# Si4844-A10_Radio_LM386_6-25_8_11.net
KiCad netlist of a schematic drawn in EAGLE
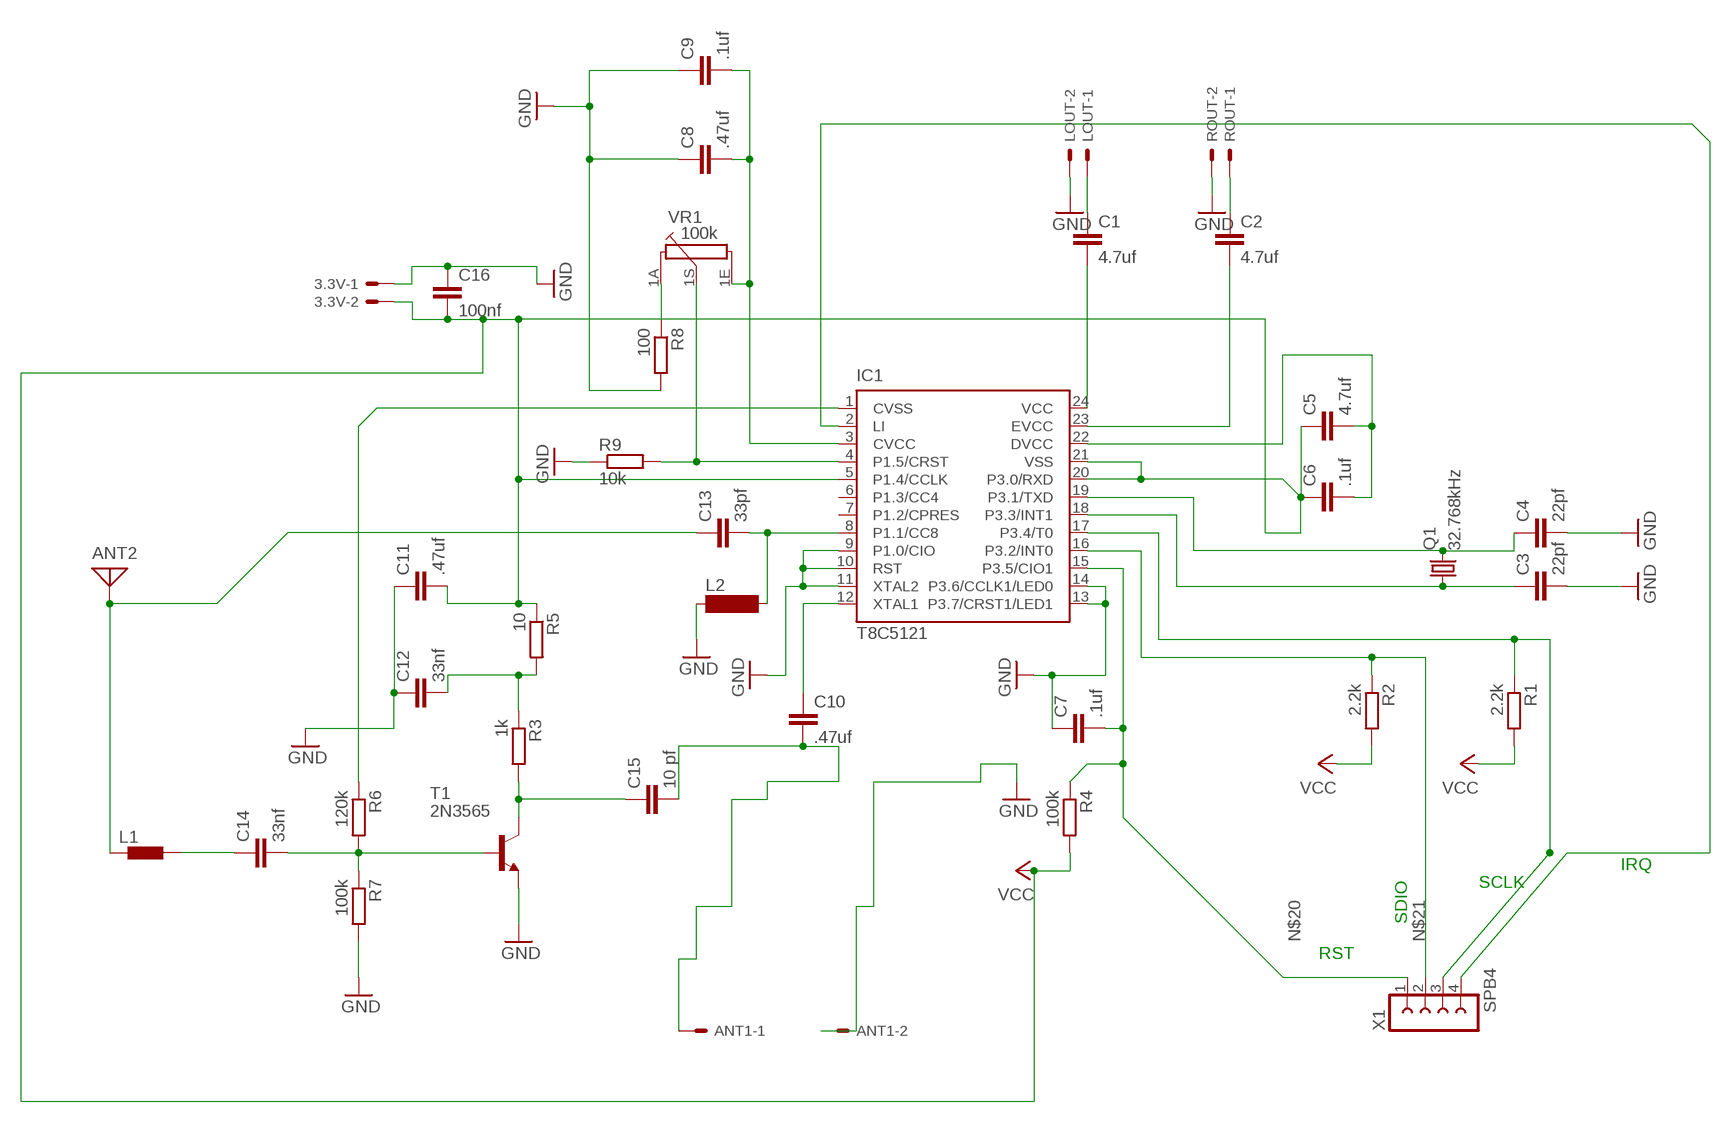
[diagram p0: schematic, sheet 1]

(export (version "E")
  (design (tool "Eeschema 10.0.6"))
  (components
    (comp (ref "3.3V")
      (value "22-23-2021")
      (footprint "eagle-import:22-23-2021")
      (fields (field (name "MF") "MOLEX"))
      (libsource (lib "eagle-import") (part "22-23-2021"))
    )
    (comp (ref "ANT1")
      (value "332-02")
      (footprint "eagle-import:332-02")
      (libsource (lib "eagle-import") (part "332-02"))
    )
    (comp (ref "ANT2")
      (value "ANTENNA")
      (footprint "eagle-import:PAD-01")
      (libsource (lib "eagle-import") (part "ANTENNA"))
    )
    (comp (ref "C1")
      (value "4.7uf")
      (footprint "eagle-import:C2.5-2")
      (libsource (lib "eagle-import") (part "C2.5/2"))
    )
    (comp (ref "C2")
      (value "4.7uf")
      (footprint "eagle-import:C2.5-2")
      (libsource (lib "eagle-import") (part "C2.5/2"))
    )
    (comp (ref "C3")
      (value "22pf")
      (footprint "eagle-import:C2.5-2")
      (libsource (lib "eagle-import") (part "C2.5/2"))
    )
    (comp (ref "C4")
      (value "22pf")
      (footprint "eagle-import:C2.5-2")
      (libsource (lib "eagle-import") (part "C2.5/2"))
    )
    (comp (ref "C5")
      (value "4.7uf")
      (footprint "eagle-import:C2.5-2")
      (libsource (lib "eagle-import") (part "C2.5/2"))
    )
    (comp (ref "C6")
      (value ".1uf")
      (footprint "eagle-import:C2.5-2")
      (libsource (lib "eagle-import") (part "C2.5/2"))
    )
    (comp (ref "C7")
      (value ".1uf")
      (footprint "eagle-import:C2.5-2")
      (libsource (lib "eagle-import") (part "C2.5/2"))
    )
    (comp (ref "C8")
      (value ".47uf")
      (footprint "eagle-import:C2.5-2")
      (libsource (lib "eagle-import") (part "C2.5/2"))
    )
    (comp (ref "C9")
      (value ".1uf")
      (footprint "eagle-import:C2.5-2")
      (libsource (lib "eagle-import") (part "C2.5/2"))
    )
    (comp (ref "C10")
      (value ".47uf")
      (footprint "eagle-import:C2.5-2")
      (libsource (lib "eagle-import") (part "C2.5/2"))
    )
    (comp (ref "C11")
      (value ".47uf")
      (footprint "eagle-import:C2.5-3")
      (libsource (lib "eagle-import") (part "C2,5-3"))
    )
    (comp (ref "C12")
      (value "33nf")
      (footprint "eagle-import:C2.5-3")
      (libsource (lib "eagle-import") (part "C2,5-3"))
    )
    (comp (ref "C13")
      (value "33pf")
      (footprint "eagle-import:C2.5-3")
      (libsource (lib "eagle-import") (part "C2,5-3"))
    )
    (comp (ref "C14")
      (value "33nf")
      (footprint "eagle-import:C2.5-3")
      (libsource (lib "eagle-import") (part "C2,5-3"))
    )
    (comp (ref "C15")
      (value "10 pf")
      (footprint "eagle-import:C2.5-3")
      (libsource (lib "eagle-import") (part "C2,5-3"))
    )
    (comp (ref "C16")
      (value "100nf")
      (footprint "eagle-import:C2.5-2")
      (libsource (lib "eagle-import") (part "C2.5/2"))
    )
    (comp (ref "IC1")
      (value "T8C5121")
      (footprint "eagle-import:SSOP24")
      (libsource (lib "eagle-import") (part "T8C5121"))
    )
    (comp (ref "L1")
      (value "BLM15HB121SN1")
      (footprint "eagle-import:0402")
      (libsource (lib "eagle-import") (part "BLM15HB121SN1"))
    )
    (comp (ref "L2")
      (value "SM-1206")
      (footprint "eagle-import:SM-1206")
      (libsource (lib "eagle-import") (part "SM-1206"))
    )
    (comp (ref "LOUT")
      (value "22-23-2021")
      (footprint "eagle-import:22-23-2021")
      (fields (field (name "MF") "MOLEX"))
      (libsource (lib "eagle-import") (part "22-23-2021"))
    )
    (comp (ref "Q1")
      (value "32.768kHz")
      (footprint "eagle-import:TC26V")
      (libsource (lib "eagle-import") (part "CRYSTALTC26V"))
    )
    (comp (ref "R1")
      (value "2.2k")
      (footprint "eagle-import:0204_7")
      (libsource (lib "eagle-import") (part "R-EU_0204/7"))
    )
    (comp (ref "R2")
      (value "2.2k")
      (footprint "eagle-import:0204_7")
      (libsource (lib "eagle-import") (part "R-EU_0204/7"))
    )
    (comp (ref "R3")
      (value "1k")
      (footprint "eagle-import:0204_7")
      (libsource (lib "eagle-import") (part "R-EU_0204/7"))
    )
    (comp (ref "R4")
      (value "100k")
      (footprint "eagle-import:0204_7")
      (libsource (lib "eagle-import") (part "R-EU_0204/7"))
    )
    (comp (ref "R5")
      (value "10")
      (footprint "eagle-import:0204_7")
      (libsource (lib "eagle-import") (part "R-EU_0204/7"))
    )
    (comp (ref "R6")
      (value "120k")
      (footprint "eagle-import:0204_7")
      (libsource (lib "eagle-import") (part "R-EU_0204/7"))
    )
    (comp (ref "R7")
      (value "100k")
      (footprint "eagle-import:0204_7")
      (libsource (lib "eagle-import") (part "R-EU_0204/7"))
    )
    (comp (ref "R8")
      (value "100")
      (footprint "eagle-import:0204_7")
      (libsource (lib "eagle-import") (part "R-EU_0204/7"))
    )
    (comp (ref "R9")
      (value "10k")
      (footprint "eagle-import:0204_7")
      (libsource (lib "eagle-import") (part "R-EU_0204/7"))
    )
    (comp (ref "ROUT")
      (value "22-23-2021")
      (footprint "eagle-import:22-23-2021")
      (fields (field (name "MF") "MOLEX"))
      (libsource (lib "eagle-import") (part "22-23-2021"))
    )
    (comp (ref "T1")
      (value "2N3565")
      (footprint "eagle-import:TO92")
      (libsource (lib "eagle-import") (part "2N3565"))
    )
    (comp (ref "VR1")
      (value "100k")
      (footprint "eagle-import:PC16S")
      (libsource (lib "eagle-import") (part "PC16S"))
    )
    (comp (ref "X1")
      (value "SPB4")
      (footprint "eagle-import:SPB4")
      (libsource (lib "eagle-import") (part "SPB4"))
    )
  )
  (nets
    (net (code "1") (name "/N$20") (class "Default")
      (node (ref "C7") (pin "2") (pinfunction "2_2") (pintype "passive"))
      (node (ref "IC1") (pin "15") (pinfunction "P3.5/CIO1_15") (pintype "bidirectional"))
      (node (ref "R4") (pin "1") (pinfunction "1_1") (pintype "passive"))
      (node (ref "X1") (pin "1") (pinfunction "1_1") (pintype "passive"))
    )
    (net (code "2") (name "/N$21") (class "Default")
      (node (ref "IC1") (pin "16") (pinfunction "P3.2/INT0_16") (pintype "bidirectional"))
      (node (ref "R2") (pin "1") (pinfunction "1_1") (pintype "passive"))
      (node (ref "X1") (pin "2") (pinfunction "2_2") (pintype "passive"))
    )
    (net (code "3") (name "GND") (class "Default")
      (node (ref "3.3V") (pin "1") (pinfunction "S_1") (pintype "passive"))
      (node (ref "ANT1") (pin "2") (pinfunction "S_2") (pintype "passive"))
      (node (ref "C11") (pin "1") (pinfunction "1_1") (pintype "passive"))
      (node (ref "C12") (pin "1") (pinfunction "1_1") (pintype "passive"))
      (node (ref "C16") (pin "1") (pinfunction "1_1") (pintype "passive"))
      (node (ref "C3") (pin "2") (pinfunction "2_2") (pintype "passive"))
      (node (ref "C4") (pin "2") (pinfunction "2_2") (pintype "passive"))
      (node (ref "C7") (pin "1") (pinfunction "1_1") (pintype "passive"))
      (node (ref "C8") (pin "1") (pinfunction "1_1") (pintype "passive"))
      (node (ref "C9") (pin "1") (pinfunction "1_1") (pintype "passive"))
      (node (ref "IC1") (pin "10") (pinfunction "RST_10") (pintype "bidirectional"))
      (node (ref "IC1") (pin "11") (pinfunction "XTAL2_11") (pintype "input"))
      (node (ref "IC1") (pin "13") (pinfunction "P3.7/CRST1/LED1_13") (pintype "bidirectional"))
      (node (ref "IC1") (pin "14") (pinfunction "P3.6/CCLK1/LED0_14") (pintype "bidirectional"))
      (node (ref "IC1") (pin "9") (pinfunction "P1.0/CIO_9") (pintype "bidirectional"))
      (node (ref "L2") (pin "1") (pinfunction "1_1") (pintype "passive"))
      (node (ref "LOUT") (pin "2") (pinfunction "S_2") (pintype "passive"))
      (node (ref "R7") (pin "2") (pinfunction "2_2") (pintype "passive"))
      (node (ref "R8") (pin "2") (pinfunction "2_2") (pintype "passive"))
      (node (ref "R9") (pin "1") (pinfunction "1_1") (pintype "passive"))
      (node (ref "ROUT") (pin "2") (pinfunction "S_2") (pintype "passive"))
      (node (ref "T1") (pin "3") (pinfunction "E_3") (pintype "passive"))
    )
    (net (code "4") (name "Net-(ANT1A-S)") (class "Default")
      (node (ref "ANT1") (pin "1") (pinfunction "S_1") (pintype "passive"))
      (node (ref "C10") (pin "2") (pinfunction "2_2") (pintype "passive"))
      (node (ref "C15") (pin "2") (pinfunction "2_2") (pintype "passive"))
    )
    (net (code "5") (name "Net-(ANT2-Pad1)") (class "Default")
      (node (ref "ANT2") (pin "1") (pinfunction "1_1") (pintype "output"))
      (node (ref "C13") (pin "1") (pinfunction "1_1") (pintype "passive"))
      (node (ref "L1") (pin "1") (pinfunction "1_1") (pintype "passive"))
    )
    (net (code "6") (name "Net-(C12-Pad2)") (class "Default")
      (node (ref "C12") (pin "2") (pinfunction "2_2") (pintype "passive"))
      (node (ref "R3") (pin "1") (pinfunction "1_1") (pintype "passive"))
      (node (ref "R5") (pin "2") (pinfunction "2_2") (pintype "passive"))
    )
    (net (code "7") (name "Net-(C14-Pad1)") (class "Default")
      (node (ref "C14") (pin "1") (pinfunction "1_1") (pintype "passive"))
      (node (ref "L1") (pin "2") (pinfunction "2_2") (pintype "passive"))
    )
    (net (code "8") (name "Net-(IC1-CVCC)") (class "Default")
      (node (ref "C8") (pin "2") (pinfunction "2_2") (pintype "passive"))
      (node (ref "C9") (pin "2") (pinfunction "2_2") (pintype "passive"))
      (node (ref "IC1") (pin "3") (pinfunction "CVCC_3") (pintype "power_in"))
      (node (ref "VR1") (pin "1E") (pinfunction "1E_1E") (pintype "passive"))
    )
    (net (code "9") (name "Net-(IC1-CVSS)") (class "Default")
      (node (ref "IC1") (pin "1") (pinfunction "CVSS_1") (pintype "power_in"))
      (node (ref "R6") (pin "1") (pinfunction "1_1") (pintype "passive"))
    )
    (net (code "10") (name "Net-(IC1-DVCC)") (class "Default")
      (node (ref "C5") (pin "2") (pinfunction "2_2") (pintype "passive"))
      (node (ref "C6") (pin "2") (pinfunction "2_2") (pintype "passive"))
      (node (ref "IC1") (pin "22") (pinfunction "DVCC_22") (pintype "power_in"))
    )
    (net (code "11") (name "Net-(IC1-EVCC)") (class "Default")
      (node (ref "C2") (pin "2") (pinfunction "2_2") (pintype "passive"))
      (node (ref "IC1") (pin "23") (pinfunction "EVCC_23") (pintype "passive"))
    )
    (net (code "12") (name "Net-(IC1-LI)") (class "Default")
      (node (ref "IC1") (pin "2") (pinfunction "LI_2") (pintype "power_in"))
      (node (ref "X1") (pin "4") (pinfunction "4_4") (pintype "passive"))
    )
    (net (code "13") (name "Net-(IC1-P1.1{slash}CC8)") (class "Default")
      (node (ref "C13") (pin "2") (pinfunction "2_2") (pintype "passive"))
      (node (ref "IC1") (pin "8") (pinfunction "P1.1/CC8_8") (pintype "bidirectional"))
      (node (ref "L2") (pin "2") (pinfunction "2_2") (pintype "passive"))
    )
    (net (code "14") (name "Net-(IC1-P1.5{slash}CRST)") (class "Default")
      (node (ref "IC1") (pin "4") (pinfunction "P1.5/CRST_4") (pintype "bidirectional"))
      (node (ref "R9") (pin "2") (pinfunction "2_2") (pintype "passive"))
      (node (ref "VR1") (pin "1S") (pinfunction "1S_1S") (pintype "passive"))
    )
    (net (code "15") (name "Net-(IC1-P3.1{slash}TXD)") (class "Default")
      (node (ref "C4") (pin "1") (pinfunction "1_1") (pintype "passive"))
      (node (ref "IC1") (pin "19") (pinfunction "P3.1/TXD_19") (pintype "bidirectional"))
      (node (ref "Q1") (pin "2") (pinfunction "2_2") (pintype "passive"))
    )
    (net (code "16") (name "Net-(IC1-P3.3{slash}INT1)") (class "Default")
      (node (ref "C3") (pin "1") (pinfunction "1_1") (pintype "passive"))
      (node (ref "IC1") (pin "18") (pinfunction "P3.3/INT1_18") (pintype "bidirectional"))
      (node (ref "Q1") (pin "1") (pinfunction "1_1") (pintype "passive"))
    )
    (net (code "17") (name "Net-(IC1-P3.4{slash}T0)") (class "Default")
      (node (ref "IC1") (pin "17") (pinfunction "P3.4/T0_17") (pintype "bidirectional"))
      (node (ref "R1") (pin "1") (pinfunction "1_1") (pintype "passive"))
      (node (ref "X1") (pin "3") (pinfunction "3_3") (pintype "passive"))
    )
    (net (code "18") (name "Net-(IC1-VCC)") (class "Default")
      (node (ref "C1") (pin "2") (pinfunction "2_2") (pintype "passive"))
      (node (ref "IC1") (pin "24") (pinfunction "VCC_24") (pintype "power_in"))
    )
    (net (code "19") (name "Net-(IC1-XTAL1)") (class "Default")
      (node (ref "C10") (pin "1") (pinfunction "1_1") (pintype "passive"))
      (node (ref "IC1") (pin "12") (pinfunction "XTAL1_12") (pintype "output"))
    )
    (net (code "20") (name "Net-(LOUTA-S)") (class "Default")
      (node (ref "C1") (pin "1") (pinfunction "1_1") (pintype "passive"))
      (node (ref "LOUT") (pin "1") (pinfunction "S_1") (pintype "passive"))
    )
    (net (code "21") (name "Net-(R8-Pad1)") (class "Default")
      (node (ref "R8") (pin "1") (pinfunction "1_1") (pintype "passive"))
      (node (ref "VR1") (pin "1A") (pinfunction "1A_1A") (pintype "passive"))
    )
    (net (code "22") (name "Net-(ROUTA-S)") (class "Default")
      (node (ref "C2") (pin "1") (pinfunction "1_1") (pintype "passive"))
      (node (ref "ROUT") (pin "1") (pinfunction "S_1") (pintype "passive"))
    )
    (net (code "23") (name "Net-(T1-B)") (class "Default")
      (node (ref "C14") (pin "2") (pinfunction "2_2") (pintype "passive"))
      (node (ref "R6") (pin "2") (pinfunction "2_2") (pintype "passive"))
      (node (ref "R7") (pin "1") (pinfunction "1_1") (pintype "passive"))
      (node (ref "T1") (pin "2") (pinfunction "B_2") (pintype "passive"))
    )
    (net (code "24") (name "Net-(T1-C)") (class "Default")
      (node (ref "C15") (pin "1") (pinfunction "1_1") (pintype "passive"))
      (node (ref "R3") (pin "2") (pinfunction "2_2") (pintype "passive"))
      (node (ref "T1") (pin "1") (pinfunction "C_1") (pintype "passive"))
    )
    (net (code "25") (name "VCC") (class "Default")
      (node (ref "3.3V") (pin "2") (pinfunction "S_2") (pintype "passive"))
      (node (ref "C11") (pin "2") (pinfunction "2_2") (pintype "passive"))
      (node (ref "C16") (pin "2") (pinfunction "2_2") (pintype "passive"))
      (node (ref "C5") (pin "1") (pinfunction "1_1") (pintype "passive"))
      (node (ref "C6") (pin "1") (pinfunction "1_1") (pintype "passive"))
      (node (ref "IC1") (pin "20") (pinfunction "P3.0/RXD_20") (pintype "bidirectional"))
      (node (ref "IC1") (pin "21") (pinfunction "VSS_21") (pintype "power_in"))
      (node (ref "IC1") (pin "5") (pinfunction "P1.4/CCLK_5") (pintype "bidirectional"))
      (node (ref "R1") (pin "2") (pinfunction "2_2") (pintype "passive"))
      (node (ref "R2") (pin "2") (pinfunction "2_2") (pintype "passive"))
      (node (ref "R4") (pin "2") (pinfunction "2_2") (pintype "passive"))
      (node (ref "R5") (pin "1") (pinfunction "1_1") (pintype "passive"))
    )
    (net (code "26") (name "unconnected-(IC1-P1.2{slash}CPRES-Pad7)") (class "Default")
      (node (ref "IC1") (pin "7") (pinfunction "P1.2/CPRES_7") (pintype "bidirectional"))
    )
    (net (code "27") (name "unconnected-(IC1-P1.3{slash}CC4-Pad6)") (class "Default")
      (node (ref "IC1") (pin "6") (pinfunction "P1.3/CC4_6") (pintype "bidirectional"))
    )
  )
)
